# rapidshark-main-breakout-bottom-mk-1_1.net
KiCad netlist of a schematic drawn in EAGLE
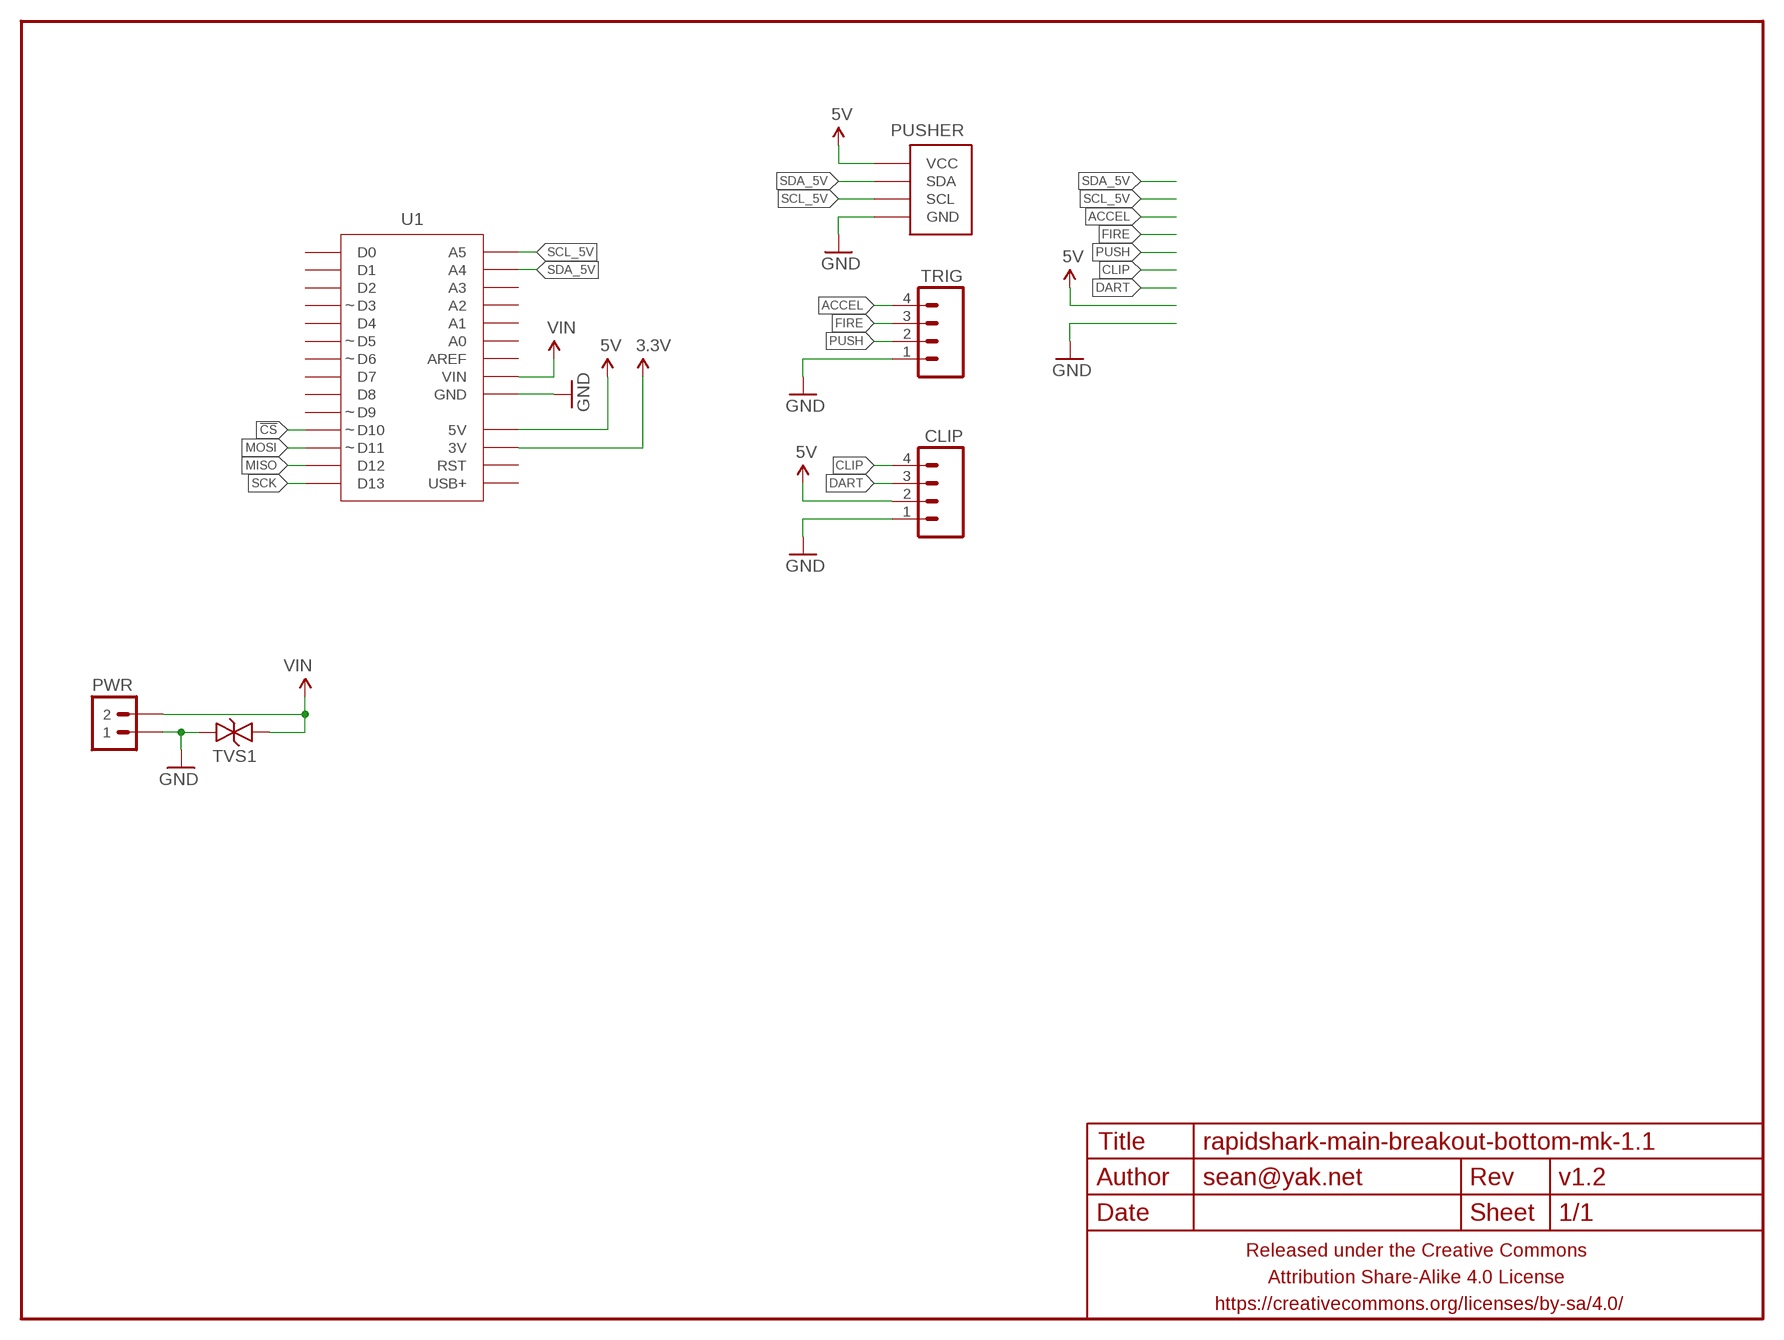
[diagram p0: schematic, sheet 1]

(export (version "E")
  (design (tool "Eeschema 10.0.6"))
  (components
    (comp (ref "CLIP")
      (value "M04JST-PTH-VERT")
      (footprint "eagle-import:JST-4-PH-VERT-PTH")
      (libsource (lib "eagle-import") (part "M04JST-PTH-VERT"))
    )
    (comp (ref "FRAME1")
      (value "FRAME-LETTERNO_PACKAGE")
      (footprint "eagle-import:DUMMY")
      (fields (field (name "DESIGNER") "sean@yak.net") (field (name "VERSION") "v1.2"))
      (libsource (lib "eagle-import") (part "FRAME-LETTERNO_PACKAGE"))
    )
    (comp (ref "PUSHER")
      (value "M04-I2CJST-4-PH-VERT-NS")
      (footprint "eagle-import:JST-4-PH-VERT-PTH")
      (libsource (lib "eagle-import") (part "M04-I2CJST-4-PH-VERT-NS"))
    )
    (comp (ref "PWR")
      (value "M02PTH-CENTERED-R+")
      (footprint "eagle-import:1X02-CENTER-R+")
      (libsource (lib "eagle-import") (part "M02PTH-CENTERED-R+"))
    )
    (comp (ref "TRIG")
      (value "M04JST-PTH-VERT")
      (footprint "eagle-import:JST-4-PH-VERT-PTH")
      (libsource (lib "eagle-import") (part "M04JST-PTH-VERT"))
    )
    (comp (ref "TVS1")
      (value "TVSDO-41-10.16MM")
      (footprint "eagle-import:DO-41-TVS-BI-10.16MM")
      (libsource (lib "eagle-import") (part "TVSDO-41-10.16MM"))
    )
    (comp (ref "U1")
      (value "ADAFRUIT_METRO_MININOHOLES-OUTSIDER")
      (footprint "eagle-import:ADAFRUIT_METRO_MINI_OUTSIDER")
      (libsource (lib "eagle-import") (part "ADAFRUIT_METRO_MININOHOLES-OUTSIDER"))
    )
  )
  (nets
    (net (code "1") (name "/~{CS}") (class "Default")
      (node (ref "U1") (pin "11") (pinfunction "D10_11") (pintype "bidirectional"))
    )
    (net (code "2") (name "3.3V") (class "Default")
      (node (ref "U1") (pin "17") (pinfunction "3V_17") (pintype "bidirectional"))
    )
    (net (code "3") (name "5V") (class "Default")
      (node (ref "CLIP") (pin "2") (pinfunction "2_2") (pintype "passive"))
      (node (ref "PUSHER") (pin "2") (pinfunction "VCC_2") (pintype "bidirectional"))
      (node (ref "U1") (pin "18") (pinfunction "5V_18") (pintype "bidirectional"))
    )
    (net (code "4") (name "ACCEL") (class "Default")
      (node (ref "TRIG") (pin "4") (pinfunction "4_4") (pintype "passive"))
    )
    (net (code "5") (name "CLIP") (class "Default")
      (node (ref "CLIP") (pin "4") (pinfunction "4_4") (pintype "passive"))
    )
    (net (code "6") (name "DART") (class "Default")
      (node (ref "CLIP") (pin "3") (pinfunction "3_3") (pintype "passive"))
    )
    (net (code "7") (name "FIRE") (class "Default")
      (node (ref "TRIG") (pin "3") (pinfunction "3_3") (pintype "passive"))
    )
    (net (code "8") (name "GND") (class "Default")
      (node (ref "CLIP") (pin "1") (pinfunction "1_1") (pintype "passive"))
      (node (ref "PUSHER") (pin "1") (pinfunction "GND_1") (pintype "bidirectional"))
      (node (ref "PWR") (pin "1") (pinfunction "1_1") (pintype "passive"))
      (node (ref "TRIG") (pin "1") (pinfunction "1_1") (pintype "passive"))
      (node (ref "TVS1") (pin "P$1") (pinfunction "1_P$1") (pintype "passive"))
      (node (ref "U1") (pin "19") (pinfunction "GND_19") (pintype "bidirectional"))
      (node (ref "U1") (pin "20") (pinfunction "GND_20") (pintype "bidirectional"))
    )
    (net (code "9") (name "MISO") (class "Default")
      (node (ref "U1") (pin "13") (pinfunction "D12_13") (pintype "bidirectional"))
    )
    (net (code "10") (name "MOSI") (class "Default")
      (node (ref "U1") (pin "12") (pinfunction "D11_12") (pintype "bidirectional"))
    )
    (net (code "11") (name "PUSH") (class "Default")
      (node (ref "TRIG") (pin "2") (pinfunction "2_2") (pintype "passive"))
    )
    (net (code "12") (name "SCK") (class "Default")
      (node (ref "U1") (pin "14") (pinfunction "D13_14") (pintype "bidirectional"))
    )
    (net (code "13") (name "SCL_5V") (class "Default")
      (node (ref "PUSHER") (pin "4") (pinfunction "SCL_4") (pintype "bidirectional"))
      (node (ref "U1") (pin "28") (pinfunction "A5_28") (pintype "bidirectional"))
    )
    (net (code "14") (name "SDA_5V") (class "Default")
      (node (ref "PUSHER") (pin "3") (pinfunction "SDA_3") (pintype "bidirectional"))
      (node (ref "U1") (pin "27") (pinfunction "A4_27") (pintype "bidirectional"))
    )
    (net (code "15") (name "VIN") (class "Default")
      (node (ref "PWR") (pin "2") (pinfunction "2_2") (pintype "passive"))
      (node (ref "TVS1") (pin "P$2") (pinfunction "2_P$2") (pintype "passive"))
      (node (ref "U1") (pin "21") (pinfunction "VIN_21") (pintype "bidirectional"))
    )
    (net (code "16") (name "unconnected-(U1-A0-Pad23)") (class "Default")
      (node (ref "U1") (pin "23") (pinfunction "A0_23") (pintype "bidirectional"))
    )
    (net (code "17") (name "unconnected-(U1-A1-Pad24)") (class "Default")
      (node (ref "U1") (pin "24") (pinfunction "A1_24") (pintype "bidirectional"))
    )
    (net (code "18") (name "unconnected-(U1-A2-Pad25)") (class "Default")
      (node (ref "U1") (pin "25") (pinfunction "A2_25") (pintype "bidirectional"))
    )
    (net (code "19") (name "unconnected-(U1-A3-Pad26)") (class "Default")
      (node (ref "U1") (pin "26") (pinfunction "A3_26") (pintype "bidirectional"))
    )
    (net (code "20") (name "unconnected-(U1-AREF-Pad22)") (class "Default")
      (node (ref "U1") (pin "22") (pinfunction "AREF_22") (pintype "bidirectional"))
    )
    (net (code "21") (name "unconnected-(U1-D0-Pad1)") (class "Default")
      (node (ref "U1") (pin "1") (pinfunction "D0_1") (pintype "bidirectional"))
    )
    (net (code "22") (name "unconnected-(U1-D1-Pad2)") (class "Default")
      (node (ref "U1") (pin "2") (pinfunction "D1_2") (pintype "bidirectional"))
    )
    (net (code "23") (name "unconnected-(U1-D2-Pad3)") (class "Default")
      (node (ref "U1") (pin "3") (pinfunction "D2_3") (pintype "bidirectional"))
    )
    (net (code "24") (name "unconnected-(U1-D3-Pad4)") (class "Default")
      (node (ref "U1") (pin "4") (pinfunction "D3_4") (pintype "bidirectional"))
    )
    (net (code "25") (name "unconnected-(U1-D4-Pad5)") (class "Default")
      (node (ref "U1") (pin "5") (pinfunction "D4_5") (pintype "bidirectional"))
    )
    (net (code "26") (name "unconnected-(U1-D5-Pad6)") (class "Default")
      (node (ref "U1") (pin "6") (pinfunction "D5_6") (pintype "bidirectional"))
    )
    (net (code "27") (name "unconnected-(U1-D6-Pad7)") (class "Default")
      (node (ref "U1") (pin "7") (pinfunction "D6_7") (pintype "bidirectional"))
    )
    (net (code "28") (name "unconnected-(U1-D7-Pad8)") (class "Default")
      (node (ref "U1") (pin "8") (pinfunction "D7_8") (pintype "bidirectional"))
    )
    (net (code "29") (name "unconnected-(U1-D8-Pad9)") (class "Default")
      (node (ref "U1") (pin "9") (pinfunction "D8_9") (pintype "bidirectional"))
    )
    (net (code "30") (name "unconnected-(U1-D9-Pad10)") (class "Default")
      (node (ref "U1") (pin "10") (pinfunction "D9_10") (pintype "bidirectional"))
    )
    (net (code "31") (name "unconnected-(U1-RST-Pad16)") (class "Default")
      (node (ref "U1") (pin "16") (pinfunction "RST_16") (pintype "bidirectional"))
    )
    (net (code "32") (name "unconnected-(U1-USB+-Pad15)") (class "Default")
      (node (ref "U1") (pin "15") (pinfunction "USB+_15") (pintype "bidirectional"))
    )
  )
)
